# 2_FET_B.net
KiCad netlist of a schematic drawn in Altium Designer
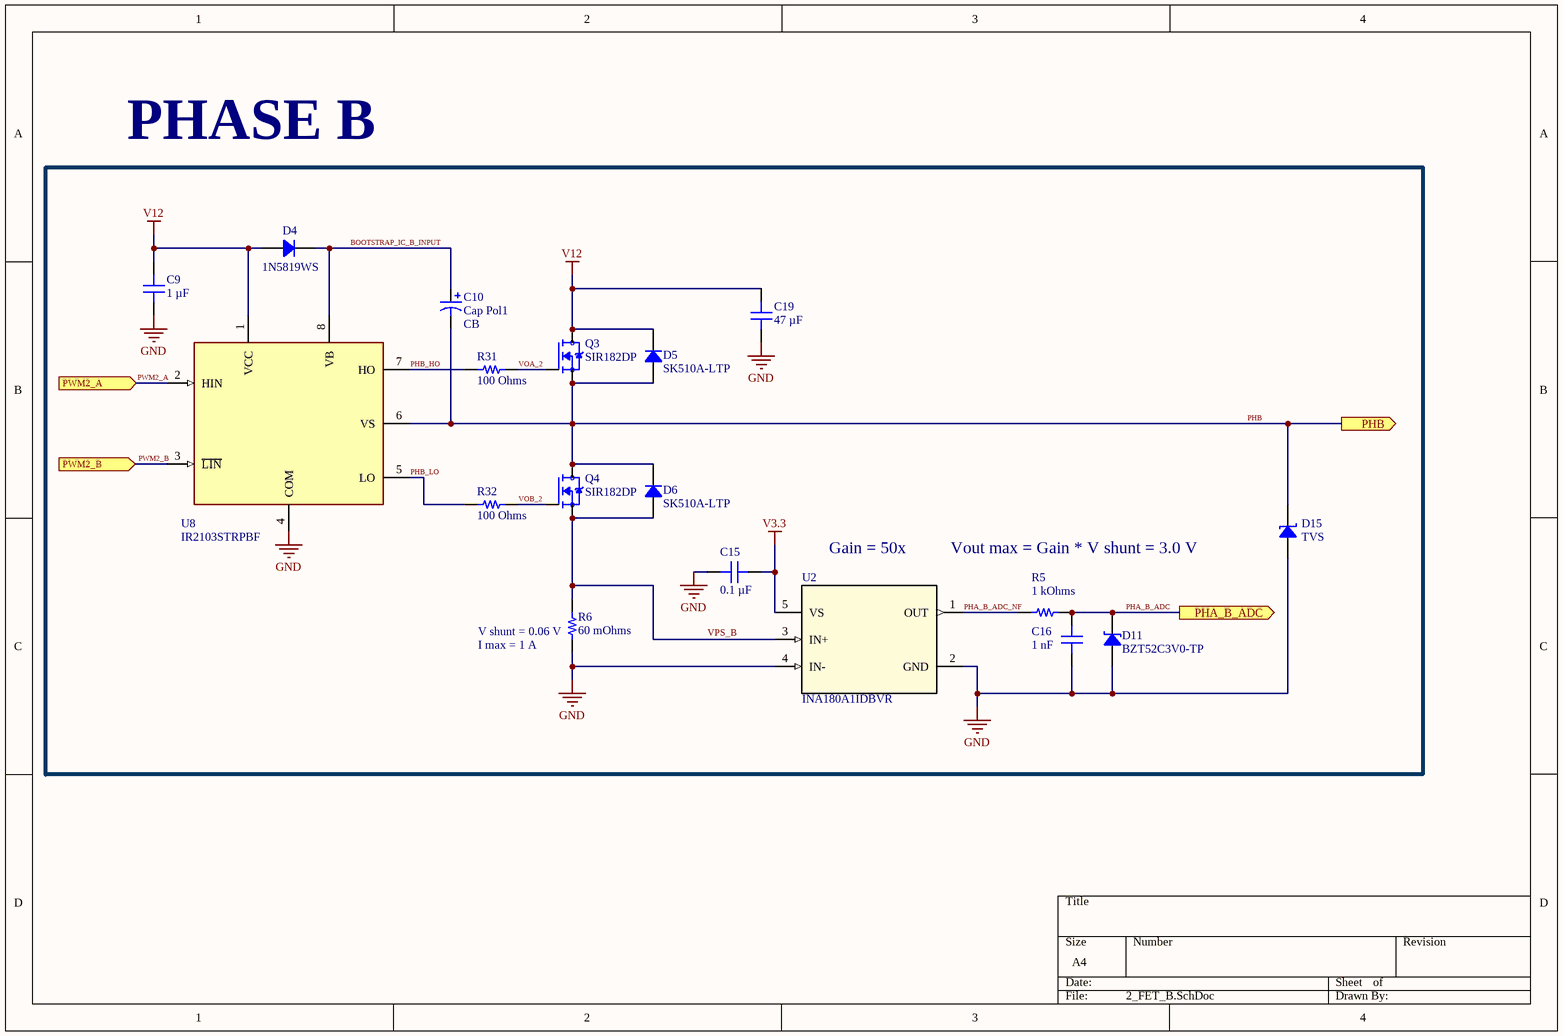
[diagram p0: 2_FET_B.SchDoc]

(export (version "E")
  (design (tool "Eeschema 10.0.6"))
  (components
    (comp (ref "C9")
      (value "1 µF")
      (footprint "CAP 0805_2012")
      (description "CAP CER 0.1UF 50V X7R 0805")
      (fields (field (name "PART NUMBER") "CC0805MRX7R9BB104") (field (name "MANUFACTURER") "Yageo"))
      (libsource (lib "Celestial Altium Library - altium_library") (part "Capacitor"))
    )
    (comp (ref "C10")
      (value "Cap Pol1")
      (footprint "CapacitorRadialElectrolytic")
      (description "Polarized Capacitor (Radial)")
      (fields (field (name "ALTIUM_VALUE") "CB") (field (name "PUBLISHER") "Altium Limited"))
      (libsource (lib "Miscellaneous Devices") (part "Cap Pol1"))
    )
    (comp (ref "C15")
      (value "0.1 µF")
      (footprint "CAP 0805_2012")
      (description "CAP CER 0.1UF 50V X7R 0805")
      (fields (field (name "PART NUMBER") "CC0805MRX7R9BB104") (field (name "MANUFACTURER") "Yageo"))
      (libsource (lib "Celestial Altium Library - altium_library") (part "Capacitor"))
    )
    (comp (ref "C16")
      (value "1 nF")
      (footprint "CAP 0805_2012")
      (description "CAP CER 0.1UF 50V X7R 0805")
      (fields (field (name "PART NUMBER") "CC0805MRX7R9BB104") (field (name "MANUFACTURER") "Yageo"))
      (libsource (lib "Celestial Altium Library - altium_library") (part "Capacitor"))
    )
    (comp (ref "C19")
      (value "47 µF")
      (footprint "CAP 1812_4532 1.1MM")
      (description "CAP1812 X5R 47UF 20% 6.3V")
      (fields
        (field (name "PART NUMBER") "GMC43X5R476M6R3NT")
        (field (name "MANUFACTURER") "Cal-Chip Electronics, Inc.")
      )
      (libsource (lib "Celestial Altium Library - altium_library") (part "Capacitor"))
    )
    (comp (ref "D4")
      (value "1N5819WS")
      (footprint "SOD-123")
      (description "DIODE SCHOTTKY 40V 1A SOD123")
      (fields (field (name "PART NUMBER") "1N5819HW-7-F") (field (name "MANUFACTURER") "Diodes Incorporated"))
      (libsource (lib "Celestial Altium Library - altium_library") (part "Diode"))
    )
    (comp (ref "D5")
      (value "SK510A-LTP")
      (footprint "DO214AC SMA")
      (description "DIODE SCHOTTKY 100V 5A DO214AC")
      (fields (field (name "MANUFACTURER") "Micro Commercial Co"))
      (libsource (lib "Celestial Altium Library - altium_library") (part "Diode"))
    )
    (comp (ref "D6")
      (value "SK510A-LTP")
      (footprint "DO214AC SMA")
      (description "DIODE SCHOTTKY 100V 5A DO214AC")
      (fields (field (name "MANUFACTURER") "Micro Commercial Co"))
      (libsource (lib "Celestial Altium Library - altium_library") (part "Diode"))
    )
    (comp (ref "D11")
      (value "BZT52C3V0-TP")
      (footprint "SOD-123")
      (description "DIODE ZENER 3V 200MW SOD123")
      (fields (field (name "MANUFACTURER") "Micro Commercial Co") (field (name "TOLERANCE") "±7%"))
      (libsource (lib "Celestial Altium Library - altium_library") (part "Diode Zener"))
    )
    (comp (ref "D15")
      (value "TVS")
      (footprint "SMF DO-219AB")
      (description "TVS DIODE 57.6V 98V DO219AB")
      (fields
        (field (name "PART NUMBER") "VTVS58ASMF-HM3-08")
        (field (name "MANUFACTURER") "Vishay Semiconductor Diodes Division")
      )
      (libsource (lib "Celestial Altium Library - altium_library") (part "DIODE TVS UNI"))
    )
    (comp (ref "Q3")
      (value "SIR182DP")
      (footprint "TRANS_SIR182DP-T1-RE3")
      (description "N-Channel 60V 60A _Tc_ 69.4W _Tc_ Surface Mount PowerPAKÂ® SO-8")
      (fields (field (name "MP") "SIR182DP-T1-RE3") (field (name "MF") "Vishay Siliconix"))
      (libsource (lib "BLDC_BridgeBoard_V1") (part "SIR182DP-T1-RE3"))
    )
    (comp (ref "Q4")
      (value "SIR182DP")
      (footprint "TRANS_SIR182DP-T1-RE3")
      (description "N-Channel 60V 60A _Tc_ 69.4W _Tc_ Surface Mount PowerPAKÂ® SO-8")
      (fields (field (name "MP") "SIR182DP-T1-RE3") (field (name "MF") "Vishay Siliconix"))
      (libsource (lib "BLDC_BridgeBoard_V1") (part "SIR182DP-T1-RE3"))
    )
    (comp (ref "R5")
      (value "1 kOhms")
      (footprint "RES 0805_2012")
      (description "RES SMD 200K OHM 5% 1/8W 0805")
      (fields (field (name "PART NUMBER") "CR0805-JW-204ELF") (field (name "MANUFACTURER") "Bourns Inc."))
      (libsource (lib "Celestial Altium Library - altium_library") (part "Resistor"))
    )
    (comp (ref "R6")
      (value "60 mOhms")
      (footprint "STACKPOLE CSR2512")
      (description "RES SMD 500 UOHM 1% 3W 2512")
      (fields (field (name "PART NUMBER") "CSR2512C0R0005F") (field (name "MANUFACTURER") "Riedon"))
      (libsource (lib "") (part "Resistor_1"))
    )
    (comp (ref "R31")
      (value "100 Ohms")
      (footprint "RES 0805_2012")
      (description "RES SMD 4.7K OHM 5% 1/2W 0805")
      (fields (field (name "PART NUMBER") "RCS08054K70JNEA") (field (name "MANUFACTURER") "Vishay Dale"))
      (libsource (lib "") (part "Resistor_1"))
    )
    (comp (ref "R32")
      (value "100 Ohms")
      (footprint "RES 0805_2012")
      (description "RES SMD 4.7K OHM 5% 1/2W 0805")
      (fields (field (name "PART NUMBER") "RCS08054K70JNEA") (field (name "MANUFACTURER") "Vishay Dale"))
      (libsource (lib "") (part "Resistor_1"))
    )
    (comp (ref "U2")
      (value "INA180A1IDBVR")
      (footprint "DBV0005A_N")
      (description "No Description Available")
      (fields (field (name "COPYRIGHT") "Copyright (C) 2023 Ultra Librarian. All rights reserved."))
      (libsource (lib "INA180A1IDBVR") (part "INA180A1IDBVR"))
    )
    (comp (ref "U8")
      (value "IR2103STRPBF")
      (footprint "Milibreria:SOIC8_IR2103STRPBF")
      (fields (field (name "MF") "Infineon"))
      (libsource (lib "BLDC_BridgeBoard_V1") (part "IR2103STRPBF"))
    )
  )
  (nets
    (net (code "1") (name "/BOOTSTRAP_IC_B_INPUT") (class "Default")
      (node (ref "C10") (pin "1") (pinfunction "1_1") (pintype "passive"))
      (node (ref "D4") (pin "2") (pinfunction "2_2") (pintype "passive"))
      (node (ref "U8") (pin "8") (pinfunction "VB_8") (pintype "power_in"))
    )
    (net (code "2") (name "/PHA_B_ADC") (class "Default")
      (node (ref "C16") (pin "1") (pinfunction "1_1") (pintype "passive"))
      (node (ref "D11") (pin "2") (pinfunction "2_2") (pintype "passive"))
      (node (ref "R5") (pin "1") (pinfunction "1_1") (pintype "passive"))
    )
    (net (code "3") (name "/PHA_B_ADC_NF") (class "Default")
      (node (ref "R5") (pin "2") (pinfunction "2_2") (pintype "passive"))
      (node (ref "U2") (pin "1") (pinfunction "OUT_1") (pintype "output"))
    )
    (net (code "4") (name "/PHB") (class "Default")
      (node (ref "C10") (pin "2") (pinfunction "2_2") (pintype "passive"))
      (node (ref "D15") (pin "2") (pinfunction "2_2") (pintype "passive"))
      (node (ref "D5") (pin "1") (pinfunction "1_1") (pintype "passive"))
      (node (ref "D6") (pin "2") (pinfunction "2_2") (pintype "passive"))
      (node (ref "Q3") (pin "1") (pinfunction "S_1") (pintype "passive"))
      (node (ref "Q3") (pin "2") (pinfunction "S_2") (pintype "passive"))
      (node (ref "Q3") (pin "3") (pinfunction "S_3") (pintype "passive"))
      (node (ref "Q4") (pin "5") (pinfunction "D_5") (pintype "passive"))
      (node (ref "Q4") (pin "6") (pinfunction "D_6") (pintype "passive"))
      (node (ref "Q4") (pin "7") (pinfunction "D_7") (pintype "passive"))
      (node (ref "Q4") (pin "8") (pinfunction "D_8") (pintype "passive"))
      (node (ref "Q4") (pin "9") (pinfunction "D_9") (pintype "passive"))
      (node (ref "U8") (pin "6") (pinfunction "VS_6") (pintype "passive"))
    )
    (net (code "5") (name "/PHB_HO") (class "Default")
      (node (ref "R31") (pin "2") (pinfunction "2_2") (pintype "passive"))
      (node (ref "U8") (pin "7") (pinfunction "HO_7") (pintype "passive"))
    )
    (net (code "6") (name "/PHB_LO") (class "Default")
      (node (ref "R32") (pin "2") (pinfunction "2_2") (pintype "passive"))
      (node (ref "U8") (pin "5") (pinfunction "LO_5") (pintype "passive"))
    )
    (net (code "7") (name "/PWM2_A") (class "Default")
      (node (ref "U8") (pin "2") (pinfunction "HIN_2") (pintype "input"))
    )
    (net (code "8") (name "/PWM2_B") (class "Default")
      (node (ref "U8") (pin "3") (pinfunction "~{LIN}_3") (pintype "input"))
    )
    (net (code "9") (name "/VOA_2") (class "Default")
      (node (ref "Q3") (pin "4") (pinfunction "G_4") (pintype "passive"))
      (node (ref "R31") (pin "1") (pinfunction "1_1") (pintype "passive"))
    )
    (net (code "10") (name "/VOB_2") (class "Default")
      (node (ref "Q4") (pin "4") (pinfunction "G_4") (pintype "passive"))
      (node (ref "R32") (pin "1") (pinfunction "1_1") (pintype "passive"))
    )
    (net (code "11") (name "/VPS_B") (class "Default")
      (node (ref "D6") (pin "1") (pinfunction "1_1") (pintype "passive"))
      (node (ref "Q4") (pin "1") (pinfunction "S_1") (pintype "passive"))
      (node (ref "Q4") (pin "2") (pinfunction "S_2") (pintype "passive"))
      (node (ref "Q4") (pin "3") (pinfunction "S_3") (pintype "passive"))
      (node (ref "R6") (pin "2") (pinfunction "2_2") (pintype "passive"))
      (node (ref "U2") (pin "3") (pinfunction "IN+_3") (pintype "input"))
    )
    (net (code "12") (name "GND") (class "Default")
      (node (ref "C15") (pin "2") (pinfunction "2_2") (pintype "passive"))
      (node (ref "C16") (pin "2") (pinfunction "2_2") (pintype "passive"))
      (node (ref "C19") (pin "1") (pinfunction "1_1") (pintype "passive"))
      (node (ref "C9") (pin "1") (pinfunction "1_1") (pintype "passive"))
      (node (ref "D11") (pin "1") (pinfunction "1_1") (pintype "passive"))
      (node (ref "D15") (pin "1") (pinfunction "1_1") (pintype "passive"))
      (node (ref "R6") (pin "1") (pinfunction "1_1") (pintype "passive"))
      (node (ref "U2") (pin "2") (pinfunction "GND_2") (pintype "power_in"))
      (node (ref "U2") (pin "4") (pinfunction "IN-_4") (pintype "input"))
      (node (ref "U8") (pin "4") (pinfunction "COM_4") (pintype "power_in"))
    )
    (net (code "13") (name "V3.3") (class "Default")
      (node (ref "C15") (pin "1") (pinfunction "1_1") (pintype "passive"))
      (node (ref "U2") (pin "5") (pinfunction "VS_5") (pintype "power_in"))
    )
    (net (code "14") (name "V12") (class "Default")
      (node (ref "C19") (pin "2") (pinfunction "2_2") (pintype "passive"))
      (node (ref "C9") (pin "2") (pinfunction "2_2") (pintype "passive"))
      (node (ref "D4") (pin "1") (pinfunction "1_1") (pintype "passive"))
      (node (ref "D5") (pin "2") (pinfunction "2_2") (pintype "passive"))
      (node (ref "Q3") (pin "5") (pinfunction "D_5") (pintype "passive"))
      (node (ref "Q3") (pin "6") (pinfunction "D_6") (pintype "passive"))
      (node (ref "Q3") (pin "7") (pinfunction "D_7") (pintype "passive"))
      (node (ref "Q3") (pin "8") (pinfunction "D_8") (pintype "passive"))
      (node (ref "Q3") (pin "9") (pinfunction "D_9") (pintype "passive"))
      (node (ref "U8") (pin "1") (pinfunction "VCC_1") (pintype "power_in"))
    )
  )
)
